# 11_-MAIN_POWER.net
KiCad netlist of a schematic drawn in Altium Designer
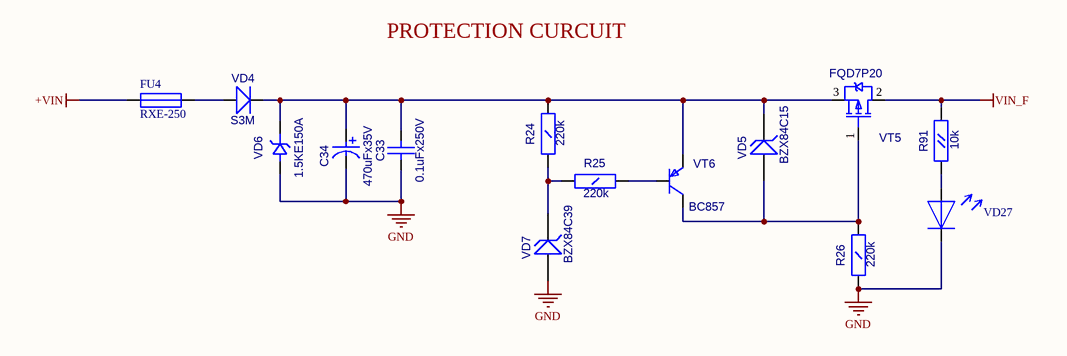
[diagram p0: [11]-MAIN_POWER.SchDoc]

(export (version "E")
  (design (tool "Eeschema 10.0.6"))
  (components
    (comp (ref "C33")
      (value "0.1uFx250V")
      (footprint "CC1206")
      (description "CC1206")
      (libsource (lib "gprs_modem_2") (part "CC1206"))
    )
    (comp (ref "C34")
      (value "470uFx35V")
      (footprint "CC16X10_CAP0.5(1)(Primary)")
      (description "CAP0.5(1)")
      (libsource (lib "gprs_modem_2") (part "CAP0.5(1)"))
    )
    (comp (ref "FU4")
      (value "RXE-250")
      (footprint "RXE-250_FLAT")
      (libsource (lib "fizik_lib") (part "RXE-250"))
    )
    (comp (ref "R24")
      (value "220k")
      (footprint "RC1206")
      (description "RC1206")
      (libsource (lib "fizik_lib") (part "RC1206"))
    )
    (comp (ref "R25")
      (value "220k")
      (footprint "RC1206")
      (description "RC1206")
      (libsource (lib "fizik_lib") (part "RC1206"))
    )
    (comp (ref "R26")
      (value "220k")
      (footprint "RC1206")
      (description "RC1206")
      (libsource (lib "fizik_lib") (part "RC1206"))
    )
    (comp (ref "R91")
      (value "10k")
      (footprint "RC0603")
      (description "RC0603")
      (libsource (lib "fizik_lib") (part "RC0603"))
    )
    (comp (ref "VD4")
      (value "S3M")
      (footprint "SMC")
      (description "Schottky Rectifier")
      (libsource (lib "fizik_lib") (part "S3A"))
    )
    (comp (ref "VD5")
      (value "BZX84C15")
      (footprint "SOT-23(123)")
      (description "Zener Voltage Regulator Diode")
      (libsource (lib "fizik_lib") (part "BZX84"))
    )
    (comp (ref "VD6")
      (value "1.5KE150A")
      (footprint "DO-201_FLAT")
      (description "1.5KE")
      (libsource (lib "fizik_lib") (part "1.5KE"))
    )
    (comp (ref "VD7")
      (value "BZX84C39")
      (footprint "SOT-23(123)")
      (description "Zener Voltage Regulator Diode")
      (libsource (lib "fizik_lib") (part "BZX84"))
    )
    (comp (ref "VD27")
      (value "LED_0805")
      (footprint "LED0805")
      (libsource (lib "fizik_lib") (part "LED_0805"))
    )
    (comp (ref "VT5")
      (value "FQD7P20")
      (footprint "D-PAK(TO-252AA)")
      (description "HEXFET Power MOSFET")
      (libsource (lib "gprs_modem_2") (part "IRFR9220"))
    )
    (comp (ref "VT6")
      (value "BC857")
      (footprint "SOT-23(123)")
      (description "PNP 100ma transistor")
      (libsource (lib "gprs_modem_2") (part "BC857B"))
    )
  )
  (nets
    (net (code "1") (name "+VIN") (class "Default") (node (ref "FU4") (pin "1") (pintype "passive")))
    (net (code "2") (name "GND") (class "Default")
      (node (ref "C33") (pin "1") (pinfunction "A_1") (pintype "passive"))
      (node (ref "C34") (pin "1") (pintype "passive"))
      (node (ref "R26") (pin "1") (pinfunction "A_1") (pintype "passive"))
      (node (ref "VD27") (pin "2") (pintype "passive"))
      (node (ref "VD6") (pin "1") (pinfunction "A_1") (pintype "passive"))
      (node (ref "VD7") (pin "1") (pinfunction "A_1") (pintype "passive"))
    )
    (net (code "3") (name "Net-(C33-B)") (class "Default")
      (node (ref "C33") (pin "2") (pinfunction "B_2") (pintype "passive"))
      (node (ref "C34") (pin "2") (pintype "passive"))
      (node (ref "R24") (pin "2") (pinfunction "B_2") (pintype "passive"))
      (node (ref "VD4") (pin "2") (pinfunction "K_2") (pintype "passive"))
      (node (ref "VD5") (pin "3") (pinfunction "K_3") (pintype "passive"))
      (node (ref "VD6") (pin "2") (pinfunction "K_2") (pintype "passive"))
      (node (ref "VT5") (pin "3") (pinfunction "S_3") (pintype "passive"))
      (node (ref "VT6") (pin "2") (pinfunction "E_2") (pintype "passive"))
    )
    (net (code "4") (name "Net-(R24-A)") (class "Default")
      (node (ref "R24") (pin "1") (pinfunction "A_1") (pintype "passive"))
      (node (ref "R25") (pin "1") (pinfunction "A_1") (pintype "passive"))
      (node (ref "VD7") (pin "3") (pinfunction "K_3") (pintype "passive"))
    )
    (net (code "5") (name "Net-(R25-B)") (class "Default")
      (node (ref "R25") (pin "2") (pinfunction "B_2") (pintype "passive"))
      (node (ref "VT6") (pin "1") (pinfunction "B_1") (pintype "passive"))
    )
    (net (code "6") (name "Net-(R26-B)") (class "Default")
      (node (ref "R26") (pin "2") (pinfunction "B_2") (pintype "passive"))
      (node (ref "VD5") (pin "1") (pinfunction "A_1") (pintype "passive"))
      (node (ref "VT5") (pin "1") (pinfunction "G_1") (pintype "passive"))
      (node (ref "VT6") (pin "3") (pinfunction "C_3") (pintype "passive"))
    )
    (net (code "7") (name "Net-(R91-A)") (class "Default")
      (node (ref "R91") (pin "1") (pinfunction "A_1") (pintype "passive"))
      (node (ref "VD27") (pin "1") (pintype "passive"))
    )
    (net (code "8") (name "Net-(VD4-A)") (class "Default")
      (node (ref "FU4") (pin "2") (pintype "passive"))
      (node (ref "VD4") (pin "1") (pinfunction "A_1") (pintype "passive"))
    )
    (net (code "9") (name "VIN_F") (class "Default")
      (node (ref "R91") (pin "2") (pinfunction "B_2") (pintype "passive"))
      (node (ref "VT5") (pin "2") (pinfunction "D_2") (pintype "passive"))
    )
  )
)
